# tweakfuzz_redraw.net
KiCad netlist of a schematic drawn in EAGLE
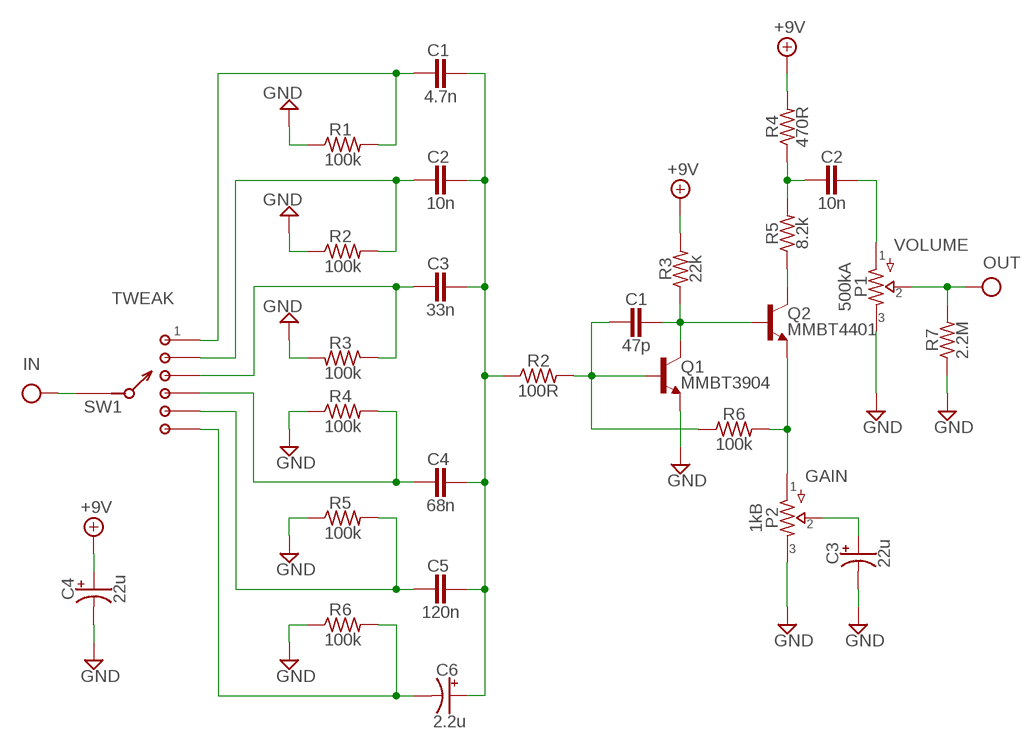
[diagram p0: schematic, sheet 1]

(export (version "E")
  (design (tool "Eeschema 10.0.6"))
  (components
    (comp (ref "C1")
      (value "47p")
      (footprint "eagle-import:BOX_SMALL")
      (libsource (lib "eagle-import") (part "CER/FILMBOX.1"))
    )
    (comp (ref "C1 ")
      (value "4.7n")
      (footprint "eagle-import:BOX_SMALL")
      (libsource (lib "eagle-import") (part "CER/FILMBOX.1"))
    )
    (comp (ref "C2")
      (value "10n")
      (footprint "eagle-import:BOX_SMALL")
      (libsource (lib "eagle-import") (part "CER/FILMBOX.1"))
    )
    (comp (ref "C2 ")
      (value "10n")
      (footprint "eagle-import:BOX_SMALL")
      (libsource (lib "eagle-import") (part "CER/FILMBOX.1"))
    )
    (comp (ref "C3")
      (value "22u")
      (footprint "eagle-import:050_020")
      (libsource (lib "eagle-import") (part "0500"))
    )
    (comp (ref "C3 ")
      (value "33n")
      (footprint "eagle-import:BOX_SMALL")
      (libsource (lib "eagle-import") (part "CER/FILMBOX.1"))
    )
    (comp (ref "C4")
      (value "22u")
      (footprint "eagle-import:050_020")
      (libsource (lib "eagle-import") (part "0500"))
    )
    (comp (ref "C4 ")
      (value "68n")
      (footprint "eagle-import:BOX_SMALL")
      (libsource (lib "eagle-import") (part "CER/FILMBOX.1"))
    )
    (comp (ref "C5 ")
      (value "120n")
      (footprint "eagle-import:BOX_SMALL")
      (libsource (lib "eagle-import") (part "CER/FILMBOX.1"))
    )
    (comp (ref "C6 ")
      (value "2.2u")
      (footprint "eagle-import:050_020")
      (libsource (lib "eagle-import") (part "0500"))
    )
    (comp (ref "P1")
      (value "500kA")
      (footprint "eagle-import:16MM")
      (libsource (lib "eagle-import") (part "POTS16MM"))
    )
    (comp (ref "P2")
      (value "1kB")
      (footprint "eagle-import:16MM")
      (libsource (lib "eagle-import") (part "POTS16MM"))
    )
    (comp (ref "Q1")
      (value "MMBT3904")
      (footprint "eagle-import:TO92-")
      (libsource (lib "eagle-import") (part "2N3904"))
    )
    (comp (ref "Q2")
      (value "MMBT4401")
      (footprint "eagle-import:TO92-")
      (libsource (lib "eagle-import") (part "2N3904"))
    )
    (comp (ref "R1 ")
      (value "100k")
      (footprint "eagle-import:R0207_3")
      (libsource (lib "eagle-import") (part "R_.3B"))
    )
    (comp (ref "R2")
      (value "100R")
      (footprint "eagle-import:R0207_3")
      (libsource (lib "eagle-import") (part "R_.3B"))
    )
    (comp (ref "R2 ")
      (value "100k")
      (footprint "eagle-import:R0207_3")
      (libsource (lib "eagle-import") (part "R_.3B"))
    )
    (comp (ref "R3")
      (value "22k")
      (footprint "eagle-import:R0207_3")
      (libsource (lib "eagle-import") (part "R_.3B"))
    )
    (comp (ref "R3 ")
      (value "100k")
      (footprint "eagle-import:R0207_3")
      (libsource (lib "eagle-import") (part "R_.3B"))
    )
    (comp (ref "R4")
      (value "470R")
      (footprint "eagle-import:R0207_3")
      (libsource (lib "eagle-import") (part "R_.3B"))
    )
    (comp (ref "R4 ")
      (value "100k")
      (footprint "eagle-import:R0207_3")
      (libsource (lib "eagle-import") (part "R_.3B"))
    )
    (comp (ref "R5")
      (value "8.2k")
      (footprint "eagle-import:R0207_3")
      (libsource (lib "eagle-import") (part "R_.3B"))
    )
    (comp (ref "R5 ")
      (value "100k")
      (footprint "eagle-import:R0207_3")
      (libsource (lib "eagle-import") (part "R_.3B"))
    )
    (comp (ref "R6")
      (value "100k")
      (footprint "eagle-import:R0207_3")
      (libsource (lib "eagle-import") (part "R_.3B"))
    )
    (comp (ref "R6 ")
      (value "100k")
      (footprint "eagle-import:R0207_3")
      (libsource (lib "eagle-import") (part "R_.3B"))
    )
    (comp (ref "R7")
      (value "2.2M")
      (footprint "eagle-import:R0207_3")
      (libsource (lib "eagle-import") (part "R_.3B"))
    )
    (comp (ref "SW1")
      (value "1P6T")
      (footprint "eagle-import:1P6T")
      (libsource (lib "eagle-import") (part "1P6T"))
    )
  )
  (nets
    (net (code "1") (name "+9V") (class "Default")
      (node (ref "C4") (pin "+") (pinfunction "+_+") (pintype "passive"))
      (node (ref "R3") (pin "2") (pinfunction "2_2") (pintype "passive"))
      (node (ref "R4") (pin "2") (pinfunction "2_2") (pintype "passive"))
    )
    (net (code "2") (name "GND") (class "Default")
      (node (ref "C3") (pin "-") (pinfunction "-_-") (pintype "passive"))
      (node (ref "C4") (pin "-") (pinfunction "-_-") (pintype "passive"))
      (node (ref "P1") (pin "3") (pinfunction "3_3") (pintype "passive"))
      (node (ref "P2") (pin "3") (pinfunction "3_3") (pintype "passive"))
      (node (ref "Q1") (pin "3") (pinfunction "E_3") (pintype "passive"))
      (node (ref "R1 ") (pin "1") (pinfunction "1_1") (pintype "passive"))
      (node (ref "R2 ") (pin "1") (pinfunction "1_1") (pintype "passive"))
      (node (ref "R3 ") (pin "2") (pinfunction "2_2") (pintype "passive"))
      (node (ref "R4 ") (pin "1") (pinfunction "1_1") (pintype "passive"))
      (node (ref "R5 ") (pin "1") (pinfunction "1_1") (pintype "passive"))
      (node (ref "R6 ") (pin "1") (pinfunction "1_1") (pintype "passive"))
      (node (ref "R7") (pin "1") (pinfunction "1_1") (pintype "passive"))
    )
    (net (code "3") (name "IN") (class "Default")
      (node (ref "SW1") (pin "7") (pinfunction "A_7") (pintype "bidirectional"))
    )
    (net (code "4") (name "Net-(C1 -Pad1)") (class "Default")
      (node (ref "C1 ") (pin "1") (pinfunction "1_1") (pintype "passive"))
      (node (ref "C2 ") (pin "1") (pinfunction "1_1") (pintype "passive"))
      (node (ref "C3 ") (pin "1") (pinfunction "1_1") (pintype "passive"))
      (node (ref "C4 ") (pin "1") (pinfunction "1_1") (pintype "passive"))
      (node (ref "C5 ") (pin "1") (pinfunction "1_1") (pintype "passive"))
      (node (ref "C6 ") (pin "+") (pinfunction "+_+") (pintype "passive"))
      (node (ref "R2") (pin "1") (pinfunction "1_1") (pintype "passive"))
    )
    (net (code "5") (name "Net-(C2-Pad1)") (class "Default")
      (node (ref "C2") (pin "1") (pinfunction "1_1") (pintype "passive"))
      (node (ref "P1") (pin "1") (pinfunction "1_1") (pintype "passive"))
    )
    (net (code "6") (name "Net-(C2-Pad2)") (class "Default")
      (node (ref "C2") (pin "2") (pinfunction "2_2") (pintype "passive"))
      (node (ref "R4") (pin "1") (pinfunction "1_1") (pintype "passive"))
      (node (ref "R5") (pin "2") (pinfunction "2_2") (pintype "passive"))
    )
    (net (code "7") (name "Net-(C3-Pad+)") (class "Default")
      (node (ref "C3") (pin "+") (pinfunction "+_+") (pintype "passive"))
      (node (ref "P2") (pin "2") (pinfunction "2_2") (pintype "passive"))
    )
    (net (code "8") (name "Net-(Q1-B)") (class "Default")
      (node (ref "C1") (pin "2") (pinfunction "2_2") (pintype "passive"))
      (node (ref "Q1") (pin "2") (pinfunction "B_2") (pintype "passive"))
      (node (ref "R2") (pin "2") (pinfunction "2_2") (pintype "passive"))
      (node (ref "R6") (pin "1") (pinfunction "1_1") (pintype "passive"))
    )
    (net (code "9") (name "Net-(Q1-C)") (class "Default")
      (node (ref "C1") (pin "1") (pinfunction "1_1") (pintype "passive"))
      (node (ref "Q1") (pin "1") (pinfunction "C_1") (pintype "passive"))
      (node (ref "Q2") (pin "2") (pinfunction "B_2") (pintype "passive"))
      (node (ref "R3") (pin "1") (pinfunction "1_1") (pintype "passive"))
    )
    (net (code "10") (name "Net-(Q2-C)") (class "Default")
      (node (ref "Q2") (pin "1") (pinfunction "C_1") (pintype "passive"))
      (node (ref "R5") (pin "1") (pinfunction "1_1") (pintype "passive"))
    )
    (net (code "11") (name "Net-(Q2-E)") (class "Default")
      (node (ref "P2") (pin "1") (pinfunction "1_1") (pintype "passive"))
      (node (ref "Q2") (pin "3") (pinfunction "E_3") (pintype "passive"))
      (node (ref "R6") (pin "2") (pinfunction "2_2") (pintype "passive"))
    )
    (net (code "12") (name "Net-(SW1-2)") (class "Default")
      (node (ref "C1 ") (pin "2") (pinfunction "2_2") (pintype "passive"))
      (node (ref "R1 ") (pin "2") (pinfunction "2_2") (pintype "passive"))
      (node (ref "SW1") (pin "1") (pinfunction "2_1") (pintype "bidirectional"))
    )
    (net (code "13") (name "Net-(SW1-3)") (class "Default")
      (node (ref "C2 ") (pin "2") (pinfunction "2_2") (pintype "passive"))
      (node (ref "R2 ") (pin "2") (pinfunction "2_2") (pintype "passive"))
      (node (ref "SW1") (pin "2") (pinfunction "3_2") (pintype "bidirectional"))
    )
    (net (code "14") (name "Net-(SW1-4)") (class "Default")
      (node (ref "C3 ") (pin "2") (pinfunction "2_2") (pintype "passive"))
      (node (ref "R3 ") (pin "1") (pinfunction "1_1") (pintype "passive"))
      (node (ref "SW1") (pin "3") (pinfunction "4_3") (pintype "bidirectional"))
    )
    (net (code "15") (name "Net-(SW1-5)") (class "Default")
      (node (ref "C4 ") (pin "2") (pinfunction "2_2") (pintype "passive"))
      (node (ref "R4 ") (pin "2") (pinfunction "2_2") (pintype "passive"))
      (node (ref "SW1") (pin "4") (pinfunction "5_4") (pintype "bidirectional"))
    )
    (net (code "16") (name "Net-(SW1-6)") (class "Default")
      (node (ref "C5 ") (pin "2") (pinfunction "2_2") (pintype "passive"))
      (node (ref "R5 ") (pin "2") (pinfunction "2_2") (pintype "passive"))
      (node (ref "SW1") (pin "5") (pinfunction "6_5") (pintype "bidirectional"))
    )
    (net (code "17") (name "Net-(SW1-7)") (class "Default")
      (node (ref "C6 ") (pin "-") (pinfunction "-_-") (pintype "passive"))
      (node (ref "R6 ") (pin "2") (pinfunction "2_2") (pintype "passive"))
      (node (ref "SW1") (pin "6") (pinfunction "7_6") (pintype "bidirectional"))
    )
    (net (code "18") (name "OUT") (class "Default")
      (node (ref "P1") (pin "2") (pinfunction "2_2") (pintype "passive"))
      (node (ref "R7") (pin "2") (pinfunction "2_2") (pintype "passive"))
    )
  )
)
